# GrblMega2560.net
KiCad netlist of a schematic drawn in EAGLE
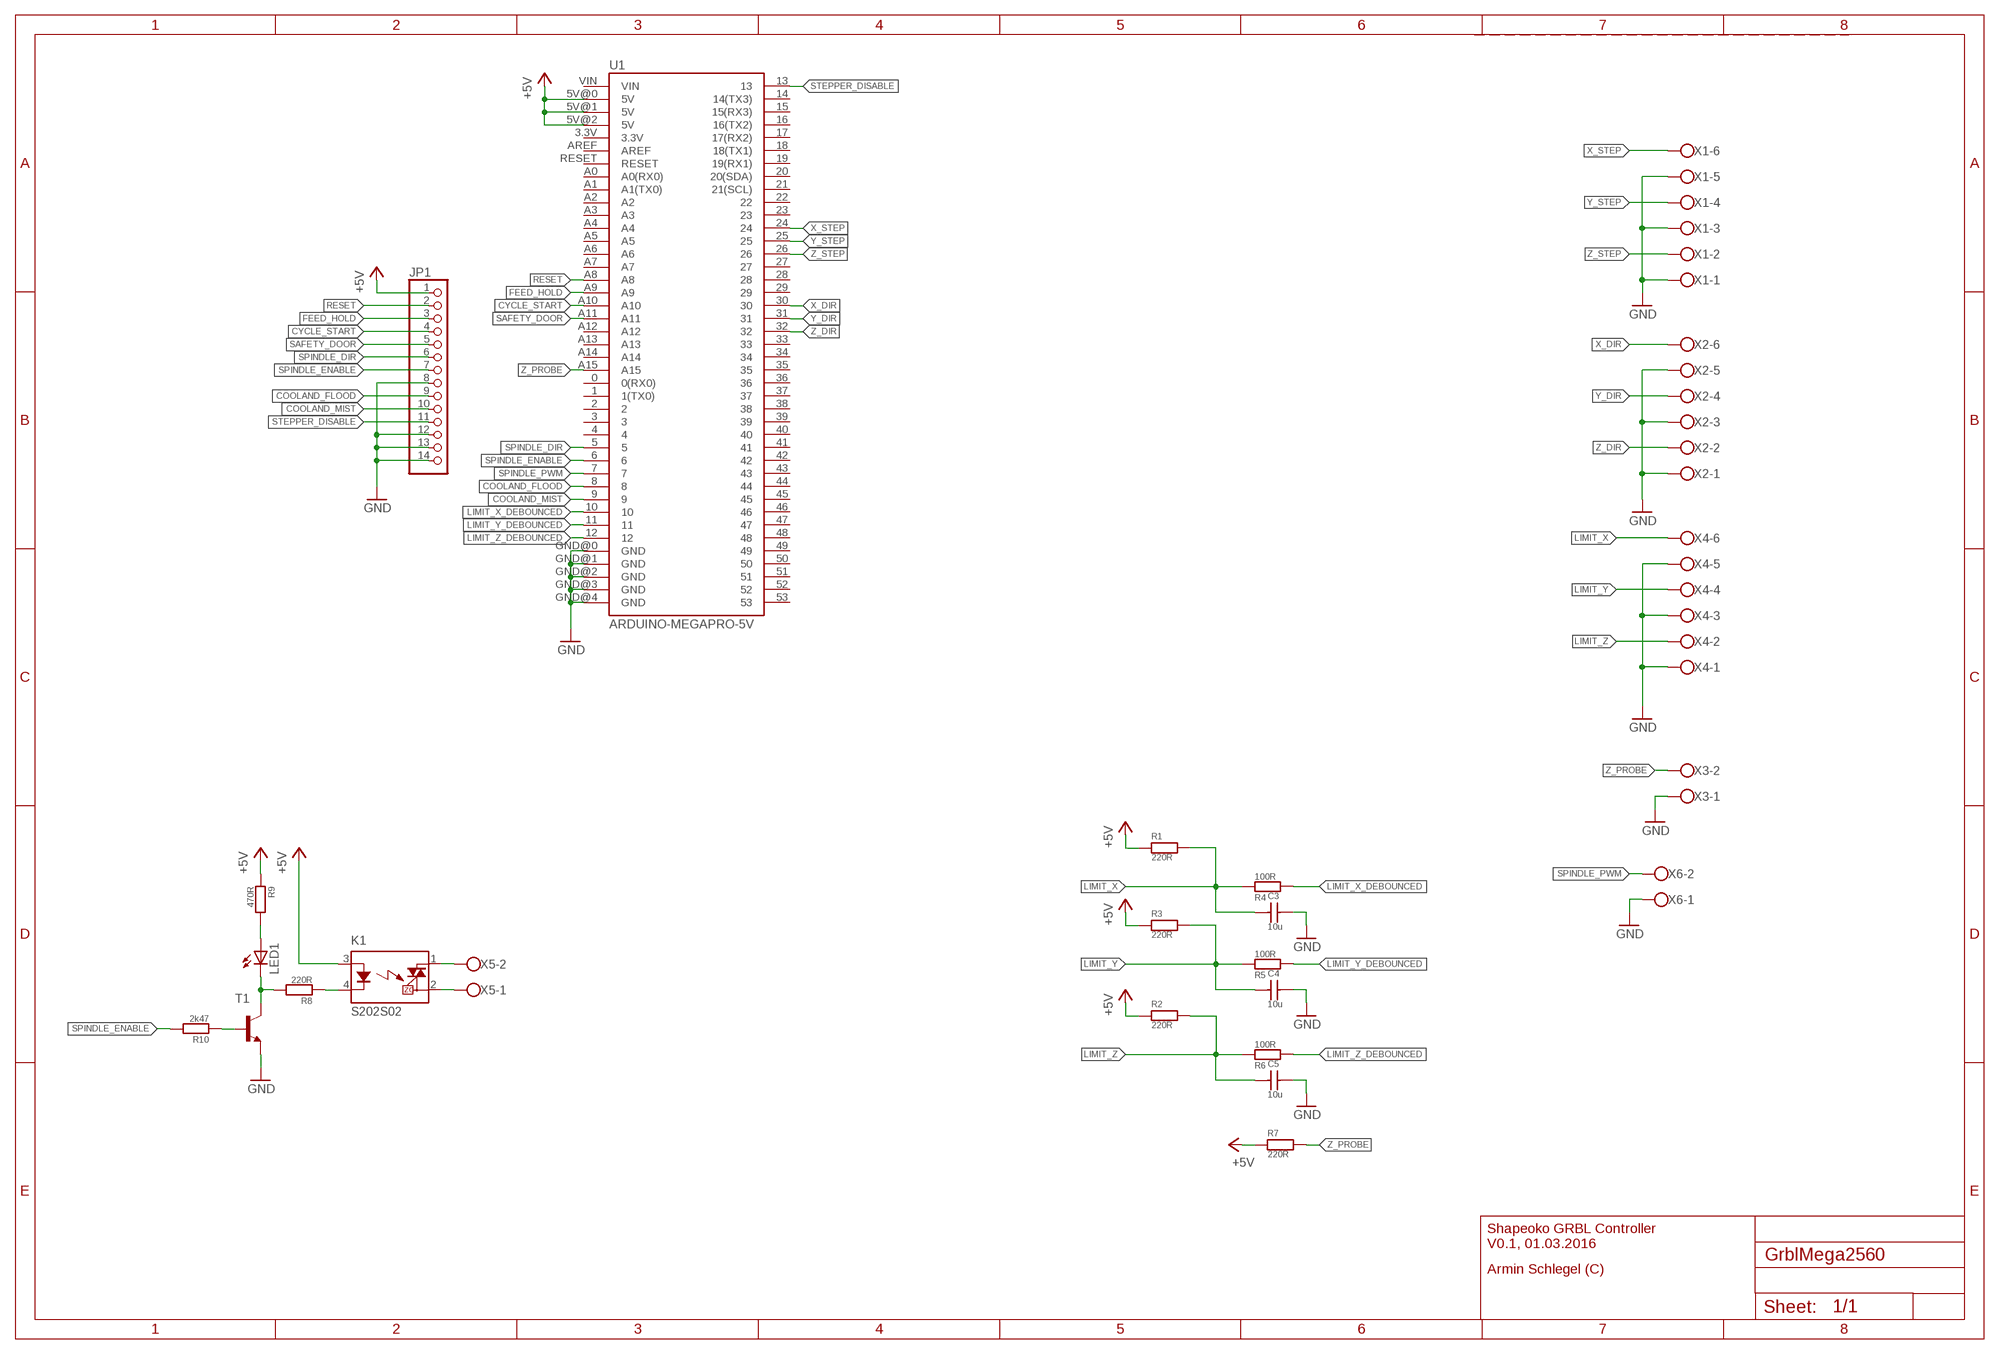
[diagram p0: schematic, sheet 1]

(export (version "E")
  (design (tool "Eeschema 10.0.6"))
  (components
    (comp (ref "C3")
      (value "10u")
      (footprint "eagle-import:C0805")
      (libsource (lib "eagle-import") (part "C_SMD0805"))
    )
    (comp (ref "C4")
      (value "10u")
      (footprint "eagle-import:C0805")
      (libsource (lib "eagle-import") (part "C_SMD0805"))
    )
    (comp (ref "C5")
      (value "10u")
      (footprint "eagle-import:C0805")
      (libsource (lib "eagle-import") (part "C_SMD0805"))
    )
    (comp (ref "JP1")
      (value "PINHD-1X14")
      (footprint "eagle-import:1X14")
      (libsource (lib "eagle-import") (part "PINHD-1X14"))
    )
    (comp (ref "K1")
      (value "S202S02")
      (footprint "eagle-import:S202S02")
      (fields (field (name "MPN") "S202S02F"))
      (libsource (lib "eagle-import") (part "S02S022"))
    )
    (comp (ref "LED1")
      (value "LED3MM")
      (footprint "eagle-import:LED3MM")
      (libsource (lib "eagle-import") (part "LED3MM"))
    )
    (comp (ref "R1")
      (value "220R")
      (footprint "eagle-import:R0603")
      (libsource (lib "eagle-import") (part "R0603"))
    )
    (comp (ref "R2")
      (value "220R")
      (footprint "eagle-import:R0603")
      (libsource (lib "eagle-import") (part "R0603"))
    )
    (comp (ref "R3")
      (value "220R")
      (footprint "eagle-import:R0603")
      (libsource (lib "eagle-import") (part "R0603"))
    )
    (comp (ref "R4")
      (value "100R")
      (footprint "eagle-import:R0603")
      (libsource (lib "eagle-import") (part "R0603"))
    )
    (comp (ref "R5")
      (value "100R")
      (footprint "eagle-import:R0603")
      (libsource (lib "eagle-import") (part "R0603"))
    )
    (comp (ref "R6")
      (value "100R")
      (footprint "eagle-import:R0603")
      (libsource (lib "eagle-import") (part "R0603"))
    )
    (comp (ref "R7")
      (value "220R")
      (footprint "eagle-import:R0603")
      (libsource (lib "eagle-import") (part "R0603"))
    )
    (comp (ref "R8")
      (value "220R")
      (footprint "eagle-import:R0603")
      (libsource (lib "eagle-import") (part "R0603"))
    )
    (comp (ref "R9")
      (value "470R")
      (footprint "eagle-import:R0603")
      (libsource (lib "eagle-import") (part "R0603"))
    )
    (comp (ref "R10")
      (value "2k47")
      (footprint "eagle-import:R0603")
      (libsource (lib "eagle-import") (part "R0603"))
    )
    (comp (ref "T1")
      (value "BC847-NPN-SOT23-BEC")
      (footprint "eagle-import:SOT23-BEC")
      (libsource (lib "eagle-import") (part "-NPN-SOT23-BECBC847"))
    )
    (comp (ref "U1")
      (value "ARDUINO-MEGAPRO-5V")
      (footprint "eagle-import:ARDUINO_MEGA-PRO-5V")
      (libsource (lib "eagle-import") (part "ARDUINO-MEGAPRO-5V"))
    )
    (comp (ref "X1")
      (value "W237-136")
      (footprint "eagle-import:W237-136")
      (fields (field (name "MPN") "237-136"))
      (libsource (lib "eagle-import") (part "W237-136"))
    )
    (comp (ref "X2")
      (value "W237-136")
      (footprint "eagle-import:W237-136")
      (fields (field (name "MPN") "237-136"))
      (libsource (lib "eagle-import") (part "W237-136"))
    )
    (comp (ref "X3")
      (value "W237-102")
      (footprint "eagle-import:W237-102")
      (fields (field (name "MPN") "237-102"))
      (libsource (lib "eagle-import") (part "W237-102"))
    )
    (comp (ref "X4")
      (value "W237-136")
      (footprint "eagle-import:W237-136")
      (fields (field (name "MPN") "237-136"))
      (libsource (lib "eagle-import") (part "W237-136"))
    )
    (comp (ref "X5")
      (value "W237-102")
      (footprint "eagle-import:W237-102")
      (fields (field (name "MPN") "237-102"))
      (libsource (lib "eagle-import") (part "W237-102"))
    )
    (comp (ref "X6")
      (value "W237-102")
      (footprint "eagle-import:W237-102")
      (fields (field (name "MPN") "237-102"))
      (libsource (lib "eagle-import") (part "W237-102"))
    )
  )
  (nets
    (net (code "1") (name "+5V") (class "Default")
      (node (ref "JP1") (pin "1") (pinfunction "1_1") (pintype "passive"))
      (node (ref "K1") (pin "3") (pinfunction "A_3") (pintype "passive"))
      (node (ref "R1") (pin "1") (pinfunction "P$1_1") (pintype "passive"))
      (node (ref "R2") (pin "1") (pinfunction "P$1_1") (pintype "passive"))
      (node (ref "R3") (pin "1") (pinfunction "P$1_1") (pintype "passive"))
      (node (ref "R7") (pin "1") (pinfunction "P$1_1") (pintype "passive"))
      (node (ref "R9") (pin "1") (pinfunction "P$1_1") (pintype "passive"))
      (node (ref "U1") (pin "5V@0") (pinfunction "5V_5V@0") (pintype "bidirectional"))
      (node (ref "U1") (pin "5V@1") (pinfunction "5V_5V@1") (pintype "bidirectional"))
      (node (ref "U1") (pin "5V@2") (pinfunction "5V_5V@2") (pintype "bidirectional"))
    )
    (net (code "2") (name "COOLAND_FLOOD") (class "Default")
      (node (ref "JP1") (pin "9") (pinfunction "9_9") (pintype "passive"))
      (node (ref "U1") (pin "8") (pinfunction "8_8") (pintype "bidirectional"))
    )
    (net (code "3") (name "COOLAND_MIST") (class "Default")
      (node (ref "JP1") (pin "10") (pinfunction "10_10") (pintype "passive"))
      (node (ref "U1") (pin "9") (pinfunction "9_9") (pintype "bidirectional"))
    )
    (net (code "4") (name "CYCLE_START") (class "Default")
      (node (ref "JP1") (pin "4") (pinfunction "4_4") (pintype "passive"))
      (node (ref "U1") (pin "A10") (pinfunction "A10_A10") (pintype "bidirectional"))
    )
    (net (code "5") (name "FEED_HOLD") (class "Default")
      (node (ref "JP1") (pin "3") (pinfunction "3_3") (pintype "passive"))
      (node (ref "U1") (pin "A9") (pinfunction "A9_A9") (pintype "bidirectional"))
    )
    (net (code "6") (name "GND") (class "Default")
      (node (ref "C3") (pin "2") (pinfunction "P$2_2") (pintype "passive"))
      (node (ref "C4") (pin "2") (pinfunction "P$2_2") (pintype "passive"))
      (node (ref "C5") (pin "2") (pinfunction "P$2_2") (pintype "passive"))
      (node (ref "JP1") (pin "12") (pinfunction "12_12") (pintype "passive"))
      (node (ref "JP1") (pin "13") (pinfunction "13_13") (pintype "passive"))
      (node (ref "JP1") (pin "14") (pinfunction "14_14") (pintype "passive"))
      (node (ref "JP1") (pin "8") (pinfunction "8_8") (pintype "passive"))
      (node (ref "T1") (pin "E") (pinfunction "E_E") (pintype "passive"))
      (node (ref "U1") (pin "GND@0") (pinfunction "GND_GND@0") (pintype "bidirectional"))
      (node (ref "U1") (pin "GND@1") (pinfunction "GND_GND@1") (pintype "bidirectional"))
      (node (ref "U1") (pin "GND@2") (pinfunction "GND_GND@2") (pintype "bidirectional"))
      (node (ref "U1") (pin "GND@3") (pinfunction "GND_GND@3") (pintype "bidirectional"))
      (node (ref "U1") (pin "GND@4") (pinfunction "GND_GND@4") (pintype "bidirectional"))
      (node (ref "X1") (pin "1") (pinfunction "KL_1") (pintype "passive"))
      (node (ref "X1") (pin "3") (pinfunction "KL_3") (pintype "passive"))
      (node (ref "X1") (pin "5") (pinfunction "KL_5") (pintype "passive"))
      (node (ref "X2") (pin "1") (pinfunction "KL_1") (pintype "passive"))
      (node (ref "X2") (pin "3") (pinfunction "KL_3") (pintype "passive"))
      (node (ref "X2") (pin "5") (pinfunction "KL_5") (pintype "passive"))
      (node (ref "X3") (pin "1") (pinfunction "KL_1") (pintype "passive"))
      (node (ref "X4") (pin "1") (pinfunction "KL_1") (pintype "passive"))
      (node (ref "X4") (pin "3") (pinfunction "KL_3") (pintype "passive"))
      (node (ref "X4") (pin "5") (pinfunction "KL_5") (pintype "passive"))
      (node (ref "X6") (pin "1") (pinfunction "KL_1") (pintype "passive"))
    )
    (net (code "7") (name "LIMIT_X") (class "Default")
      (node (ref "C3") (pin "1") (pinfunction "P$1_1") (pintype "passive"))
      (node (ref "R1") (pin "2") (pinfunction "P$2_2") (pintype "passive"))
      (node (ref "R4") (pin "1") (pinfunction "P$1_1") (pintype "passive"))
      (node (ref "X4") (pin "6") (pinfunction "KL_6") (pintype "passive"))
    )
    (net (code "8") (name "LIMIT_X_DEBOUNCED") (class "Default")
      (node (ref "R4") (pin "2") (pinfunction "P$2_2") (pintype "passive"))
      (node (ref "U1") (pin "10") (pinfunction "10_10") (pintype "bidirectional"))
    )
    (net (code "9") (name "LIMIT_Y") (class "Default")
      (node (ref "C4") (pin "1") (pinfunction "P$1_1") (pintype "passive"))
      (node (ref "R3") (pin "2") (pinfunction "P$2_2") (pintype "passive"))
      (node (ref "R5") (pin "1") (pinfunction "P$1_1") (pintype "passive"))
      (node (ref "X4") (pin "4") (pinfunction "KL_4") (pintype "passive"))
    )
    (net (code "10") (name "LIMIT_Y_DEBOUNCED") (class "Default")
      (node (ref "R5") (pin "2") (pinfunction "P$2_2") (pintype "passive"))
      (node (ref "U1") (pin "11") (pinfunction "11_11") (pintype "bidirectional"))
    )
    (net (code "11") (name "LIMIT_Z") (class "Default")
      (node (ref "C5") (pin "1") (pinfunction "P$1_1") (pintype "passive"))
      (node (ref "R2") (pin "2") (pinfunction "P$2_2") (pintype "passive"))
      (node (ref "R6") (pin "1") (pinfunction "P$1_1") (pintype "passive"))
      (node (ref "X4") (pin "2") (pinfunction "KL_2") (pintype "passive"))
    )
    (net (code "12") (name "LIMIT_Z_DEBOUNCED") (class "Default")
      (node (ref "R6") (pin "2") (pinfunction "P$2_2") (pintype "passive"))
      (node (ref "U1") (pin "12") (pinfunction "12_12") (pintype "bidirectional"))
    )
    (net (code "13") (name "Net-(K1-DS1)") (class "Default")
      (node (ref "K1") (pin "1") (pinfunction "DS1_1") (pintype "passive"))
      (node (ref "X5") (pin "2") (pinfunction "KL_2") (pintype "passive"))
    )
    (net (code "14") (name "Net-(K1-DS2)") (class "Default")
      (node (ref "K1") (pin "2") (pinfunction "DS2_2") (pintype "passive"))
      (node (ref "X5") (pin "1") (pinfunction "KL_1") (pintype "passive"))
    )
    (net (code "15") (name "Net-(K1-K)") (class "Default")
      (node (ref "K1") (pin "4") (pinfunction "K_4") (pintype "passive"))
      (node (ref "R8") (pin "1") (pinfunction "P$1_1") (pintype "passive"))
    )
    (net (code "16") (name "Net-(LED1-C)") (class "Default")
      (node (ref "LED1") (pin "K") (pinfunction "C_K") (pintype "passive"))
      (node (ref "R8") (pin "2") (pinfunction "P$2_2") (pintype "passive"))
      (node (ref "T1") (pin "C") (pinfunction "C_C") (pintype "passive"))
    )
    (net (code "17") (name "Net-(R9-P$2)") (class "Default")
      (node (ref "LED1") (pin "A") (pinfunction "A_A") (pintype "passive"))
      (node (ref "R9") (pin "2") (pinfunction "P$2_2") (pintype "passive"))
    )
    (net (code "18") (name "Net-(R10-P$1)") (class "Default")
      (node (ref "R10") (pin "1") (pinfunction "P$1_1") (pintype "passive"))
      (node (ref "T1") (pin "B") (pinfunction "B_B") (pintype "passive"))
    )
    (net (code "19") (name "RESET") (class "Default")
      (node (ref "JP1") (pin "2") (pinfunction "2_2") (pintype "passive"))
      (node (ref "U1") (pin "A8") (pinfunction "A8_A8") (pintype "bidirectional"))
    )
    (net (code "20") (name "SAFETY_DOOR") (class "Default")
      (node (ref "JP1") (pin "5") (pinfunction "5_5") (pintype "passive"))
      (node (ref "U1") (pin "A11") (pinfunction "A11_A11") (pintype "bidirectional"))
    )
    (net (code "21") (name "SPINDLE_DIR") (class "Default")
      (node (ref "JP1") (pin "6") (pinfunction "6_6") (pintype "passive"))
      (node (ref "U1") (pin "5") (pinfunction "5_5") (pintype "bidirectional"))
    )
    (net (code "22") (name "SPINDLE_ENABLE") (class "Default")
      (node (ref "JP1") (pin "7") (pinfunction "7_7") (pintype "passive"))
      (node (ref "R10") (pin "2") (pinfunction "P$2_2") (pintype "passive"))
      (node (ref "U1") (pin "6") (pinfunction "6_6") (pintype "bidirectional"))
    )
    (net (code "23") (name "SPINDLE_PWM") (class "Default")
      (node (ref "U1") (pin "7") (pinfunction "7_7") (pintype "bidirectional"))
      (node (ref "X6") (pin "2") (pinfunction "KL_2") (pintype "passive"))
    )
    (net (code "24") (name "STEPPER_DISABLE") (class "Default")
      (node (ref "JP1") (pin "11") (pinfunction "11_11") (pintype "passive"))
      (node (ref "U1") (pin "13") (pinfunction "13_13") (pintype "bidirectional"))
    )
    (net (code "25") (name "X_DIR") (class "Default")
      (node (ref "U1") (pin "30") (pinfunction "30_30") (pintype "bidirectional"))
      (node (ref "X2") (pin "6") (pinfunction "KL_6") (pintype "passive"))
    )
    (net (code "26") (name "X_STEP") (class "Default")
      (node (ref "U1") (pin "24") (pinfunction "24_24") (pintype "bidirectional"))
      (node (ref "X1") (pin "6") (pinfunction "KL_6") (pintype "passive"))
    )
    (net (code "27") (name "Y_DIR") (class "Default")
      (node (ref "U1") (pin "31") (pinfunction "31_31") (pintype "bidirectional"))
      (node (ref "X2") (pin "4") (pinfunction "KL_4") (pintype "passive"))
    )
    (net (code "28") (name "Y_STEP") (class "Default")
      (node (ref "U1") (pin "25") (pinfunction "25_25") (pintype "bidirectional"))
      (node (ref "X1") (pin "4") (pinfunction "KL_4") (pintype "passive"))
    )
    (net (code "29") (name "Z_DIR") (class "Default")
      (node (ref "U1") (pin "32") (pinfunction "32_32") (pintype "bidirectional"))
      (node (ref "X2") (pin "2") (pinfunction "KL_2") (pintype "passive"))
    )
    (net (code "30") (name "Z_PROBE") (class "Default")
      (node (ref "R7") (pin "2") (pinfunction "P$2_2") (pintype "passive"))
      (node (ref "U1") (pin "A15") (pinfunction "A15_A15") (pintype "bidirectional"))
      (node (ref "X3") (pin "2") (pinfunction "KL_2") (pintype "passive"))
    )
    (net (code "31") (name "Z_STEP") (class "Default")
      (node (ref "U1") (pin "26") (pinfunction "26_26") (pintype "bidirectional"))
      (node (ref "X1") (pin "2") (pinfunction "KL_2") (pintype "passive"))
    )
    (net (code "32") (name "unconnected-(U1-0(RX0)-Pad0)") (class "Default")
      (node (ref "U1") (pin "0") (pinfunction "0(RX0)_0") (pintype "bidirectional"))
    )
    (net (code "33") (name "unconnected-(U1-1(TX0)-Pad1)") (class "Default")
      (node (ref "U1") (pin "1") (pinfunction "1(TX0)_1") (pintype "bidirectional"))
    )
    (net (code "34") (name "unconnected-(U1-14(TX3)-Pad14)") (class "Default")
      (node (ref "U1") (pin "14") (pinfunction "14(TX3)_14") (pintype "bidirectional"))
    )
    (net (code "35") (name "unconnected-(U1-15(RX3)-Pad15)") (class "Default")
      (node (ref "U1") (pin "15") (pinfunction "15(RX3)_15") (pintype "bidirectional"))
    )
    (net (code "36") (name "unconnected-(U1-16(TX2)-Pad16)") (class "Default")
      (node (ref "U1") (pin "16") (pinfunction "16(TX2)_16") (pintype "bidirectional"))
    )
    (net (code "37") (name "unconnected-(U1-17(RX2)-Pad17)") (class "Default")
      (node (ref "U1") (pin "17") (pinfunction "17(RX2)_17") (pintype "bidirectional"))
    )
    (net (code "38") (name "unconnected-(U1-18(TX1)-Pad18)") (class "Default")
      (node (ref "U1") (pin "18") (pinfunction "18(TX1)_18") (pintype "bidirectional"))
    )
    (net (code "39") (name "unconnected-(U1-19(RX1)-Pad19)") (class "Default")
      (node (ref "U1") (pin "19") (pinfunction "19(RX1)_19") (pintype "bidirectional"))
    )
    (net (code "40") (name "unconnected-(U1-20(SDA)-Pad20)") (class "Default")
      (node (ref "U1") (pin "20") (pinfunction "20(SDA)_20") (pintype "bidirectional"))
    )
    (net (code "41") (name "unconnected-(U1-21(SCL)-Pad21)") (class "Default")
      (node (ref "U1") (pin "21") (pinfunction "21(SCL)_21") (pintype "bidirectional"))
    )
    (net (code "42") (name "unconnected-(U1-A0(RX0)-PadA0)") (class "Default")
      (node (ref "U1") (pin "A0") (pinfunction "A0(RX0)_A0") (pintype "bidirectional"))
    )
    (net (code "43") (name "unconnected-(U1-A1(TX0)-PadA1)") (class "Default")
      (node (ref "U1") (pin "A1") (pinfunction "A1(TX0)_A1") (pintype "bidirectional"))
    )
    (net (code "44") (name "unconnected-(U1-Pad2)") (class "Default")
      (node (ref "U1") (pin "2") (pinfunction "2_2") (pintype "bidirectional"))
    )
    (net (code "45") (name "unconnected-(U1-Pad3)") (class "Default")
      (node (ref "U1") (pin "3") (pinfunction "3_3") (pintype "bidirectional"))
    )
    (net (code "46") (name "unconnected-(U1-Pad3.3V)") (class "Default")
      (node (ref "U1") (pin "3.3V") (pinfunction "3.3V_3.3V") (pintype "bidirectional"))
    )
    (net (code "47") (name "unconnected-(U1-Pad4)") (class "Default")
      (node (ref "U1") (pin "4") (pinfunction "4_4") (pintype "bidirectional"))
    )
    (net (code "48") (name "unconnected-(U1-Pad22)") (class "Default")
      (node (ref "U1") (pin "22") (pinfunction "22_22") (pintype "bidirectional"))
    )
    (net (code "49") (name "unconnected-(U1-Pad23)") (class "Default")
      (node (ref "U1") (pin "23") (pinfunction "23_23") (pintype "bidirectional"))
    )
    (net (code "50") (name "unconnected-(U1-Pad27)") (class "Default")
      (node (ref "U1") (pin "27") (pinfunction "27_27") (pintype "bidirectional"))
    )
    (net (code "51") (name "unconnected-(U1-Pad28)") (class "Default")
      (node (ref "U1") (pin "28") (pinfunction "28_28") (pintype "bidirectional"))
    )
    (net (code "52") (name "unconnected-(U1-Pad29)") (class "Default")
      (node (ref "U1") (pin "29") (pinfunction "29_29") (pintype "bidirectional"))
    )
    (net (code "53") (name "unconnected-(U1-Pad33)") (class "Default")
      (node (ref "U1") (pin "33") (pinfunction "33_33") (pintype "bidirectional"))
    )
    (net (code "54") (name "unconnected-(U1-Pad34)") (class "Default")
      (node (ref "U1") (pin "34") (pinfunction "34_34") (pintype "bidirectional"))
    )
    (net (code "55") (name "unconnected-(U1-Pad35)") (class "Default")
      (node (ref "U1") (pin "35") (pinfunction "35_35") (pintype "bidirectional"))
    )
    (net (code "56") (name "unconnected-(U1-Pad36)") (class "Default")
      (node (ref "U1") (pin "36") (pinfunction "36_36") (pintype "bidirectional"))
    )
    (net (code "57") (name "unconnected-(U1-Pad37)") (class "Default")
      (node (ref "U1") (pin "37") (pinfunction "37_37") (pintype "bidirectional"))
    )
    (net (code "58") (name "unconnected-(U1-Pad38)") (class "Default")
      (node (ref "U1") (pin "38") (pinfunction "38_38") (pintype "bidirectional"))
    )
    (net (code "59") (name "unconnected-(U1-Pad39)") (class "Default")
      (node (ref "U1") (pin "39") (pinfunction "39_39") (pintype "bidirectional"))
    )
    (net (code "60") (name "unconnected-(U1-Pad40)") (class "Default")
      (node (ref "U1") (pin "40") (pinfunction "40_40") (pintype "bidirectional"))
    )
    (net (code "61") (name "unconnected-(U1-Pad41)") (class "Default")
      (node (ref "U1") (pin "41") (pinfunction "41_41") (pintype "bidirectional"))
    )
    (net (code "62") (name "unconnected-(U1-Pad42)") (class "Default")
      (node (ref "U1") (pin "42") (pinfunction "42_42") (pintype "bidirectional"))
    )
    (net (code "63") (name "unconnected-(U1-Pad43)") (class "Default")
      (node (ref "U1") (pin "43") (pinfunction "43_43") (pintype "bidirectional"))
    )
    (net (code "64") (name "unconnected-(U1-Pad44)") (class "Default")
      (node (ref "U1") (pin "44") (pinfunction "44_44") (pintype "bidirectional"))
    )
    (net (code "65") (name "unconnected-(U1-Pad45)") (class "Default")
      (node (ref "U1") (pin "45") (pinfunction "45_45") (pintype "bidirectional"))
    )
    (net (code "66") (name "unconnected-(U1-Pad46)") (class "Default")
      (node (ref "U1") (pin "46") (pinfunction "46_46") (pintype "bidirectional"))
    )
    (net (code "67") (name "unconnected-(U1-Pad47)") (class "Default")
      (node (ref "U1") (pin "47") (pinfunction "47_47") (pintype "bidirectional"))
    )
    (net (code "68") (name "unconnected-(U1-Pad48)") (class "Default")
      (node (ref "U1") (pin "48") (pinfunction "48_48") (pintype "bidirectional"))
    )
    (net (code "69") (name "unconnected-(U1-Pad49)") (class "Default")
      (node (ref "U1") (pin "49") (pinfunction "49_49") (pintype "bidirectional"))
    )
    (net (code "70") (name "unconnected-(U1-Pad50)") (class "Default")
      (node (ref "U1") (pin "50") (pinfunction "50_50") (pintype "bidirectional"))
    )
    (net (code "71") (name "unconnected-(U1-Pad51)") (class "Default")
      (node (ref "U1") (pin "51") (pinfunction "51_51") (pintype "bidirectional"))
    )
    (net (code "72") (name "unconnected-(U1-Pad52)") (class "Default")
      (node (ref "U1") (pin "52") (pinfunction "52_52") (pintype "bidirectional"))
    )
    (net (code "73") (name "unconnected-(U1-Pad53)") (class "Default")
      (node (ref "U1") (pin "53") (pinfunction "53_53") (pintype "bidirectional"))
    )
    (net (code "74") (name "unconnected-(U1-PadA2)") (class "Default")
      (node (ref "U1") (pin "A2") (pinfunction "A2_A2") (pintype "bidirectional"))
    )
    (net (code "75") (name "unconnected-(U1-PadA3)") (class "Default")
      (node (ref "U1") (pin "A3") (pinfunction "A3_A3") (pintype "bidirectional"))
    )
    (net (code "76") (name "unconnected-(U1-PadA4)") (class "Default")
      (node (ref "U1") (pin "A4") (pinfunction "A4_A4") (pintype "bidirectional"))
    )
    (net (code "77") (name "unconnected-(U1-PadA5)") (class "Default")
      (node (ref "U1") (pin "A5") (pinfunction "A5_A5") (pintype "bidirectional"))
    )
    (net (code "78") (name "unconnected-(U1-PadA6)") (class "Default")
      (node (ref "U1") (pin "A6") (pinfunction "A6_A6") (pintype "bidirectional"))
    )
    (net (code "79") (name "unconnected-(U1-PadA7)") (class "Default")
      (node (ref "U1") (pin "A7") (pinfunction "A7_A7") (pintype "bidirectional"))
    )
    (net (code "80") (name "unconnected-(U1-PadA12)") (class "Default")
      (node (ref "U1") (pin "A12") (pinfunction "A12_A12") (pintype "bidirectional"))
    )
    (net (code "81") (name "unconnected-(U1-PadA13)") (class "Default")
      (node (ref "U1") (pin "A13") (pinfunction "A13_A13") (pintype "bidirectional"))
    )
    (net (code "82") (name "unconnected-(U1-PadA14)") (class "Default")
      (node (ref "U1") (pin "A14") (pinfunction "A14_A14") (pintype "bidirectional"))
    )
    (net (code "83") (name "unconnected-(U1-PadAREF)") (class "Default")
      (node (ref "U1") (pin "AREF") (pinfunction "AREF_AREF") (pintype "bidirectional"))
    )
    (net (code "84") (name "unconnected-(U1-PadRESET)") (class "Default")
      (node (ref "U1") (pin "RESET") (pinfunction "RESET_RESET") (pintype "bidirectional"))
    )
    (net (code "85") (name "unconnected-(U1-PadVIN)") (class "Default")
      (node (ref "U1") (pin "VIN") (pinfunction "VIN_VIN") (pintype "bidirectional"))
    )
  )
)
